# 5x4-soundboard_328p_dip.net
KiCad netlist of a schematic drawn in EAGLE
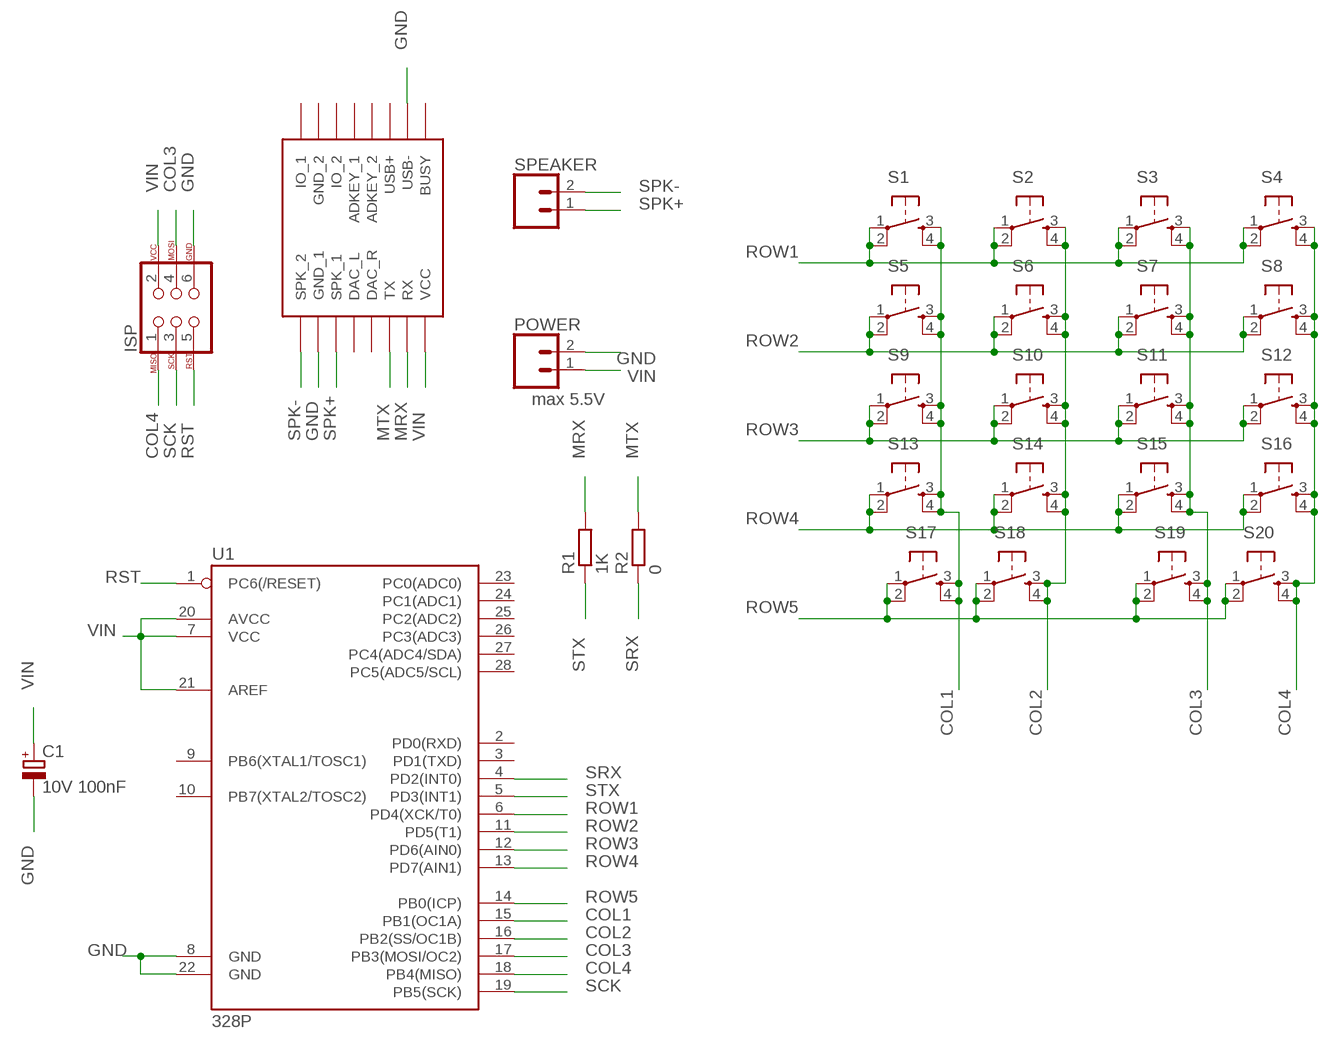
[diagram p0: schematic, sheet 1]

(export (version "E")
  (design (tool "Eeschema 10.0.6"))
  (components
    (comp (ref "C1")
      (value "10V 100nF")
      (footprint "eagle-import:E5-6")
      (libsource (lib "eagle-import") (part "CPOL-EUE5-6"))
    )
    (comp (ref "ISP")
      (value "AVR_SPI_PROG_3X2PTH")
      (footprint "eagle-import:2X3")
      (libsource (lib "eagle-import") (part "AVR_SPI_PROG_3X2PTH"))
    )
    (comp (ref "POWER")
      (value "CONN_02LOCK_LONGPADS")
      (footprint "eagle-import:1X02_LOCK_LONGPADS")
      (libsource (lib "eagle-import") (part "CONN_02LOCK_LONGPADS"))
    )
    (comp (ref "R1")
      (value "1K")
      (footprint "eagle-import:0207_10")
      (libsource (lib "eagle-import") (part "R-EU_0207/10"))
    )
    (comp (ref "R2")
      (value "0")
      (footprint "eagle-import:0207_10")
      (libsource (lib "eagle-import") (part "R-EU_0207/10"))
    )
    (comp (ref "S1")
      (value "TAC_SWITCHPTH")
      (footprint "eagle-import:TACTILE-PTH")
      (libsource (lib "eagle-import") (part "TAC_SWITCHPTH"))
    )
    (comp (ref "S2")
      (value "TAC_SWITCHPTH")
      (footprint "eagle-import:TACTILE-PTH")
      (libsource (lib "eagle-import") (part "TAC_SWITCHPTH"))
    )
    (comp (ref "S3")
      (value "TAC_SWITCHPTH")
      (footprint "eagle-import:TACTILE-PTH")
      (libsource (lib "eagle-import") (part "TAC_SWITCHPTH"))
    )
    (comp (ref "S4")
      (value "TAC_SWITCHPTH")
      (footprint "eagle-import:TACTILE-PTH")
      (libsource (lib "eagle-import") (part "TAC_SWITCHPTH"))
    )
    (comp (ref "S5")
      (value "TAC_SWITCHPTH")
      (footprint "eagle-import:TACTILE-PTH")
      (libsource (lib "eagle-import") (part "TAC_SWITCHPTH"))
    )
    (comp (ref "S6")
      (value "TAC_SWITCHPTH")
      (footprint "eagle-import:TACTILE-PTH")
      (libsource (lib "eagle-import") (part "TAC_SWITCHPTH"))
    )
    (comp (ref "S7")
      (value "TAC_SWITCHPTH")
      (footprint "eagle-import:TACTILE-PTH")
      (libsource (lib "eagle-import") (part "TAC_SWITCHPTH"))
    )
    (comp (ref "S8")
      (value "TAC_SWITCHPTH")
      (footprint "eagle-import:TACTILE-PTH")
      (libsource (lib "eagle-import") (part "TAC_SWITCHPTH"))
    )
    (comp (ref "S9")
      (value "TAC_SWITCHPTH")
      (footprint "eagle-import:TACTILE-PTH")
      (libsource (lib "eagle-import") (part "TAC_SWITCHPTH"))
    )
    (comp (ref "S10")
      (value "TAC_SWITCHPTH")
      (footprint "eagle-import:TACTILE-PTH")
      (libsource (lib "eagle-import") (part "TAC_SWITCHPTH"))
    )
    (comp (ref "S11")
      (value "TAC_SWITCHPTH")
      (footprint "eagle-import:TACTILE-PTH")
      (libsource (lib "eagle-import") (part "TAC_SWITCHPTH"))
    )
    (comp (ref "S12")
      (value "TAC_SWITCHPTH")
      (footprint "eagle-import:TACTILE-PTH")
      (libsource (lib "eagle-import") (part "TAC_SWITCHPTH"))
    )
    (comp (ref "S13")
      (value "TAC_SWITCHPTH")
      (footprint "eagle-import:TACTILE-PTH")
      (libsource (lib "eagle-import") (part "TAC_SWITCHPTH"))
    )
    (comp (ref "S14")
      (value "TAC_SWITCHPTH")
      (footprint "eagle-import:TACTILE-PTH")
      (libsource (lib "eagle-import") (part "TAC_SWITCHPTH"))
    )
    (comp (ref "S15")
      (value "TAC_SWITCHPTH")
      (footprint "eagle-import:TACTILE-PTH")
      (libsource (lib "eagle-import") (part "TAC_SWITCHPTH"))
    )
    (comp (ref "S16")
      (value "TAC_SWITCHPTH")
      (footprint "eagle-import:TACTILE-PTH")
      (libsource (lib "eagle-import") (part "TAC_SWITCHPTH"))
    )
    (comp (ref "S17")
      (value "TAC_SWITCHPTH")
      (footprint "eagle-import:TACTILE-PTH")
      (libsource (lib "eagle-import") (part "TAC_SWITCHPTH"))
    )
    (comp (ref "S18")
      (value "TAC_SWITCHPTH")
      (footprint "eagle-import:TACTILE-PTH")
      (libsource (lib "eagle-import") (part "TAC_SWITCHPTH"))
    )
    (comp (ref "S19")
      (value "TAC_SWITCHPTH")
      (footprint "eagle-import:TACTILE-PTH")
      (libsource (lib "eagle-import") (part "TAC_SWITCHPTH"))
    )
    (comp (ref "S20")
      (value "TAC_SWITCHPTH")
      (footprint "eagle-import:TACTILE-PTH")
      (libsource (lib "eagle-import") (part "TAC_SWITCHPTH"))
    )
    (comp (ref "SPEAKER")
      (value "CONN_02LOCK_LONGPADS")
      (footprint "eagle-import:1X02_LOCK_LONGPADS")
      (libsource (lib "eagle-import") (part "CONN_02LOCK_LONGPADS"))
    )
    (comp (ref "U$1")
      (value "DFPLAYER")
      (footprint "eagle-import:DFPLAYER")
      (libsource (lib "eagle-import") (part "DFPLAYER"))
    )
    (comp (ref "U1")
      (value "328P")
      (footprint "eagle-import:DIP28")
      (libsource (lib "eagle-import") (part "ATMEGA328P_PDIP"))
    )
  )
  (nets
    (net (code "1") (name "/COL1") (class "Default")
      (node (ref "S1") (pin "3") (pinfunction "3_3") (pintype "passive"))
      (node (ref "S1") (pin "4") (pinfunction "4_4") (pintype "passive"))
      (node (ref "S13") (pin "3") (pinfunction "3_3") (pintype "passive"))
      (node (ref "S13") (pin "4") (pinfunction "4_4") (pintype "passive"))
      (node (ref "S17") (pin "3") (pinfunction "3_3") (pintype "passive"))
      (node (ref "S17") (pin "4") (pinfunction "4_4") (pintype "passive"))
      (node (ref "S5") (pin "3") (pinfunction "3_3") (pintype "passive"))
      (node (ref "S5") (pin "4") (pinfunction "4_4") (pintype "passive"))
      (node (ref "S9") (pin "3") (pinfunction "3_3") (pintype "passive"))
      (node (ref "S9") (pin "4") (pinfunction "4_4") (pintype "passive"))
      (node (ref "U1") (pin "15") (pinfunction "PB1(OC1A)_15") (pintype "bidirectional"))
    )
    (net (code "2") (name "/COL2") (class "Default")
      (node (ref "S10") (pin "3") (pinfunction "3_3") (pintype "passive"))
      (node (ref "S10") (pin "4") (pinfunction "4_4") (pintype "passive"))
      (node (ref "S14") (pin "3") (pinfunction "3_3") (pintype "passive"))
      (node (ref "S14") (pin "4") (pinfunction "4_4") (pintype "passive"))
      (node (ref "S18") (pin "3") (pinfunction "3_3") (pintype "passive"))
      (node (ref "S18") (pin "4") (pinfunction "4_4") (pintype "passive"))
      (node (ref "S2") (pin "3") (pinfunction "3_3") (pintype "passive"))
      (node (ref "S2") (pin "4") (pinfunction "4_4") (pintype "passive"))
      (node (ref "S6") (pin "3") (pinfunction "3_3") (pintype "passive"))
      (node (ref "S6") (pin "4") (pinfunction "4_4") (pintype "passive"))
      (node (ref "U1") (pin "16") (pinfunction "PB2(SS/OC1B)_16") (pintype "bidirectional"))
    )
    (net (code "3") (name "/COL3") (class "Default")
      (node (ref "ISP") (pin "4") (pinfunction "4_4") (pintype "passive"))
      (node (ref "S11") (pin "3") (pinfunction "3_3") (pintype "passive"))
      (node (ref "S11") (pin "4") (pinfunction "4_4") (pintype "passive"))
      (node (ref "S15") (pin "3") (pinfunction "3_3") (pintype "passive"))
      (node (ref "S15") (pin "4") (pinfunction "4_4") (pintype "passive"))
      (node (ref "S19") (pin "3") (pinfunction "3_3") (pintype "passive"))
      (node (ref "S19") (pin "4") (pinfunction "4_4") (pintype "passive"))
      (node (ref "S3") (pin "3") (pinfunction "3_3") (pintype "passive"))
      (node (ref "S3") (pin "4") (pinfunction "4_4") (pintype "passive"))
      (node (ref "S7") (pin "3") (pinfunction "3_3") (pintype "passive"))
      (node (ref "S7") (pin "4") (pinfunction "4_4") (pintype "passive"))
      (node (ref "U1") (pin "17") (pinfunction "PB3(MOSI/OC2)_17") (pintype "bidirectional"))
    )
    (net (code "4") (name "/COL4") (class "Default")
      (node (ref "ISP") (pin "1") (pinfunction "1_1") (pintype "passive"))
      (node (ref "S12") (pin "3") (pinfunction "3_3") (pintype "passive"))
      (node (ref "S12") (pin "4") (pinfunction "4_4") (pintype "passive"))
      (node (ref "S16") (pin "3") (pinfunction "3_3") (pintype "passive"))
      (node (ref "S16") (pin "4") (pinfunction "4_4") (pintype "passive"))
      (node (ref "S20") (pin "3") (pinfunction "3_3") (pintype "passive"))
      (node (ref "S20") (pin "4") (pinfunction "4_4") (pintype "passive"))
      (node (ref "S4") (pin "3") (pinfunction "3_3") (pintype "passive"))
      (node (ref "S4") (pin "4") (pinfunction "4_4") (pintype "passive"))
      (node (ref "S8") (pin "3") (pinfunction "3_3") (pintype "passive"))
      (node (ref "S8") (pin "4") (pinfunction "4_4") (pintype "passive"))
      (node (ref "U1") (pin "18") (pinfunction "PB4(MISO)_18") (pintype "bidirectional"))
    )
    (net (code "5") (name "/GND") (class "Default")
      (node (ref "C1") (pin "-") (pinfunction "-_-") (pintype "passive"))
      (node (ref "ISP") (pin "6") (pinfunction "6_6") (pintype "passive"))
      (node (ref "POWER") (pin "2") (pinfunction "2_2") (pintype "passive"))
      (node (ref "U$1") (pin "GND_1") (pinfunction "GND_1_GND_1") (pintype "bidirectional"))
      (node (ref "U$1") (pin "USB-") (pinfunction "USB-_USB-") (pintype "bidirectional"))
      (node (ref "U1") (pin "22") (pinfunction "GND_22") (pintype "bidirectional"))
      (node (ref "U1") (pin "8") (pinfunction "GND_8") (pintype "bidirectional"))
    )
    (net (code "6") (name "/MRX") (class "Default")
      (node (ref "R1") (pin "2") (pinfunction "2_2") (pintype "passive"))
      (node (ref "U$1") (pin "RX") (pinfunction "RX_RX") (pintype "bidirectional"))
    )
    (net (code "7") (name "/MTX") (class "Default")
      (node (ref "R2") (pin "2") (pinfunction "2_2") (pintype "passive"))
      (node (ref "U$1") (pin "TX") (pinfunction "TX_TX") (pintype "bidirectional"))
    )
    (net (code "8") (name "/ROW1") (class "Default")
      (node (ref "S1") (pin "1") (pinfunction "1_1") (pintype "passive"))
      (node (ref "S1") (pin "2") (pinfunction "2_2") (pintype "passive"))
      (node (ref "S2") (pin "1") (pinfunction "1_1") (pintype "passive"))
      (node (ref "S2") (pin "2") (pinfunction "2_2") (pintype "passive"))
      (node (ref "S3") (pin "1") (pinfunction "1_1") (pintype "passive"))
      (node (ref "S3") (pin "2") (pinfunction "2_2") (pintype "passive"))
      (node (ref "S4") (pin "1") (pinfunction "1_1") (pintype "passive"))
      (node (ref "S4") (pin "2") (pinfunction "2_2") (pintype "passive"))
      (node (ref "U1") (pin "6") (pinfunction "PD4(XCK/T0)_6") (pintype "bidirectional"))
    )
    (net (code "9") (name "/ROW2") (class "Default")
      (node (ref "S5") (pin "1") (pinfunction "1_1") (pintype "passive"))
      (node (ref "S5") (pin "2") (pinfunction "2_2") (pintype "passive"))
      (node (ref "S6") (pin "1") (pinfunction "1_1") (pintype "passive"))
      (node (ref "S6") (pin "2") (pinfunction "2_2") (pintype "passive"))
      (node (ref "S7") (pin "1") (pinfunction "1_1") (pintype "passive"))
      (node (ref "S7") (pin "2") (pinfunction "2_2") (pintype "passive"))
      (node (ref "S8") (pin "1") (pinfunction "1_1") (pintype "passive"))
      (node (ref "S8") (pin "2") (pinfunction "2_2") (pintype "passive"))
      (node (ref "U1") (pin "11") (pinfunction "PD5(T1)_11") (pintype "bidirectional"))
    )
    (net (code "10") (name "/ROW3") (class "Default")
      (node (ref "S10") (pin "1") (pinfunction "1_1") (pintype "passive"))
      (node (ref "S10") (pin "2") (pinfunction "2_2") (pintype "passive"))
      (node (ref "S11") (pin "1") (pinfunction "1_1") (pintype "passive"))
      (node (ref "S11") (pin "2") (pinfunction "2_2") (pintype "passive"))
      (node (ref "S12") (pin "1") (pinfunction "1_1") (pintype "passive"))
      (node (ref "S12") (pin "2") (pinfunction "2_2") (pintype "passive"))
      (node (ref "S9") (pin "1") (pinfunction "1_1") (pintype "passive"))
      (node (ref "S9") (pin "2") (pinfunction "2_2") (pintype "passive"))
      (node (ref "U1") (pin "12") (pinfunction "PD6(AIN0)_12") (pintype "bidirectional"))
    )
    (net (code "11") (name "/ROW4") (class "Default")
      (node (ref "S13") (pin "1") (pinfunction "1_1") (pintype "passive"))
      (node (ref "S13") (pin "2") (pinfunction "2_2") (pintype "passive"))
      (node (ref "S14") (pin "1") (pinfunction "1_1") (pintype "passive"))
      (node (ref "S14") (pin "2") (pinfunction "2_2") (pintype "passive"))
      (node (ref "S15") (pin "1") (pinfunction "1_1") (pintype "passive"))
      (node (ref "S15") (pin "2") (pinfunction "2_2") (pintype "passive"))
      (node (ref "S16") (pin "1") (pinfunction "1_1") (pintype "passive"))
      (node (ref "S16") (pin "2") (pinfunction "2_2") (pintype "passive"))
      (node (ref "U1") (pin "13") (pinfunction "PD7(AIN1)_13") (pintype "bidirectional"))
    )
    (net (code "12") (name "/ROW5") (class "Default")
      (node (ref "S17") (pin "1") (pinfunction "1_1") (pintype "passive"))
      (node (ref "S17") (pin "2") (pinfunction "2_2") (pintype "passive"))
      (node (ref "S18") (pin "1") (pinfunction "1_1") (pintype "passive"))
      (node (ref "S18") (pin "2") (pinfunction "2_2") (pintype "passive"))
      (node (ref "S19") (pin "1") (pinfunction "1_1") (pintype "passive"))
      (node (ref "S19") (pin "2") (pinfunction "2_2") (pintype "passive"))
      (node (ref "S20") (pin "1") (pinfunction "1_1") (pintype "passive"))
      (node (ref "S20") (pin "2") (pinfunction "2_2") (pintype "passive"))
      (node (ref "U1") (pin "14") (pinfunction "PB0(ICP)_14") (pintype "bidirectional"))
    )
    (net (code "13") (name "/RST") (class "Default")
      (node (ref "ISP") (pin "5") (pinfunction "5_5") (pintype "passive"))
      (node (ref "U1") (pin "1") (pinfunction "PC6(/RESET)_1") (pintype "bidirectional"))
    )
    (net (code "14") (name "/SCK") (class "Default")
      (node (ref "ISP") (pin "3") (pinfunction "3_3") (pintype "passive"))
      (node (ref "U1") (pin "19") (pinfunction "PB5(SCK)_19") (pintype "bidirectional"))
    )
    (net (code "15") (name "/SPK+") (class "Default")
      (node (ref "SPEAKER") (pin "1") (pinfunction "1_1") (pintype "passive"))
      (node (ref "U$1") (pin "SPK1") (pinfunction "SPK_1_SPK1") (pintype "bidirectional"))
    )
    (net (code "16") (name "/SPK-") (class "Default")
      (node (ref "SPEAKER") (pin "2") (pinfunction "2_2") (pintype "passive"))
      (node (ref "U$1") (pin "SPK2") (pinfunction "SPK_2_SPK2") (pintype "bidirectional"))
    )
    (net (code "17") (name "/SRX") (class "Default")
      (node (ref "R2") (pin "1") (pinfunction "1_1") (pintype "passive"))
      (node (ref "U1") (pin "4") (pinfunction "PD2(INT0)_4") (pintype "bidirectional"))
    )
    (net (code "18") (name "/STX") (class "Default")
      (node (ref "R1") (pin "1") (pinfunction "1_1") (pintype "passive"))
      (node (ref "U1") (pin "5") (pinfunction "PD3(INT1)_5") (pintype "bidirectional"))
    )
    (net (code "19") (name "/VIN") (class "Default")
      (node (ref "C1") (pin "+") (pinfunction "+_+") (pintype "passive"))
      (node (ref "ISP") (pin "2") (pinfunction "2_2") (pintype "passive"))
      (node (ref "POWER") (pin "1") (pinfunction "1_1") (pintype "passive"))
      (node (ref "U$1") (pin "VCC") (pinfunction "VCC_VCC") (pintype "bidirectional"))
      (node (ref "U1") (pin "20") (pinfunction "AVCC_20") (pintype "bidirectional"))
      (node (ref "U1") (pin "21") (pinfunction "AREF_21") (pintype "bidirectional"))
      (node (ref "U1") (pin "7") (pinfunction "VCC_7") (pintype "bidirectional"))
    )
    (net (code "20") (name "unconnected-(U$1-ADKEY_1-PadADKEY1)") (class "Default")
      (node (ref "U$1") (pin "ADKEY1") (pinfunction "ADKEY_1_ADKEY1") (pintype "bidirectional"))
    )
    (net (code "21") (name "unconnected-(U$1-ADKEY_2-PadADKEY2)") (class "Default")
      (node (ref "U$1") (pin "ADKEY2") (pinfunction "ADKEY_2_ADKEY2") (pintype "bidirectional"))
    )
    (net (code "22") (name "unconnected-(U$1-IO_1-PadIO1)") (class "Default")
      (node (ref "U$1") (pin "IO1") (pinfunction "IO_1_IO1") (pintype "bidirectional"))
    )
    (net (code "23") (name "unconnected-(U$1-IO_2-PadIO2)") (class "Default")
      (node (ref "U$1") (pin "IO2") (pinfunction "IO_2_IO2") (pintype "bidirectional"))
    )
    (net (code "24") (name "unconnected-(U$1-PadBUSY)") (class "Default")
      (node (ref "U$1") (pin "BUSY") (pinfunction "BUSY_BUSY") (pintype "bidirectional"))
    )
    (net (code "25") (name "unconnected-(U$1-PadDAC_L)") (class "Default")
      (node (ref "U$1") (pin "DAC_L") (pinfunction "DAC_L_DAC_L") (pintype "bidirectional"))
    )
    (net (code "26") (name "unconnected-(U$1-PadDAC_R)") (class "Default")
      (node (ref "U$1") (pin "DAC_R") (pinfunction "DAC_R_DAC_R") (pintype "bidirectional"))
    )
    (net (code "27") (name "unconnected-(U$1-PadGND_2)") (class "Default")
      (node (ref "U$1") (pin "GND_2") (pinfunction "GND_2_GND_2") (pintype "bidirectional"))
    )
    (net (code "28") (name "unconnected-(U$1-PadUSB+)") (class "Default")
      (node (ref "U$1") (pin "USB+") (pinfunction "USB+_USB+") (pintype "bidirectional"))
    )
    (net (code "29") (name "unconnected-(U1-PB6(XTAL1{slash}TOSC1)-Pad9)") (class "Default")
      (node (ref "U1") (pin "9") (pinfunction "PB6(XTAL1/TOSC1)_9") (pintype "bidirectional"))
    )
    (net (code "30") (name "unconnected-(U1-PB7(XTAL2{slash}TOSC2)-Pad10)") (class "Default")
      (node (ref "U1") (pin "10") (pinfunction "PB7(XTAL2/TOSC2)_10") (pintype "bidirectional"))
    )
    (net (code "31") (name "unconnected-(U1-PC0(ADC0)-Pad23)") (class "Default")
      (node (ref "U1") (pin "23") (pinfunction "PC0(ADC0)_23") (pintype "bidirectional"))
    )
    (net (code "32") (name "unconnected-(U1-PC1(ADC1)-Pad24)") (class "Default")
      (node (ref "U1") (pin "24") (pinfunction "PC1(ADC1)_24") (pintype "bidirectional"))
    )
    (net (code "33") (name "unconnected-(U1-PC2(ADC2)-Pad25)") (class "Default")
      (node (ref "U1") (pin "25") (pinfunction "PC2(ADC2)_25") (pintype "bidirectional"))
    )
    (net (code "34") (name "unconnected-(U1-PC3(ADC3)-Pad26)") (class "Default")
      (node (ref "U1") (pin "26") (pinfunction "PC3(ADC3)_26") (pintype "bidirectional"))
    )
    (net (code "35") (name "unconnected-(U1-PC4(ADC4{slash}SDA)-Pad27)") (class "Default")
      (node (ref "U1") (pin "27") (pinfunction "PC4(ADC4/SDA)_27") (pintype "bidirectional"))
    )
    (net (code "36") (name "unconnected-(U1-PC5(ADC5{slash}SCL)-Pad28)") (class "Default")
      (node (ref "U1") (pin "28") (pinfunction "PC5(ADC5/SCL)_28") (pintype "bidirectional"))
    )
    (net (code "37") (name "unconnected-(U1-PD0(RXD)-Pad2)") (class "Default")
      (node (ref "U1") (pin "2") (pinfunction "PD0(RXD)_2") (pintype "bidirectional"))
    )
    (net (code "38") (name "unconnected-(U1-PD1(TXD)-Pad3)") (class "Default")
      (node (ref "U1") (pin "3") (pinfunction "PD1(TXD)_3") (pintype "bidirectional"))
    )
  )
)
